# PowerSchematic.net
KiCad netlist of a schematic drawn in Altium Designer
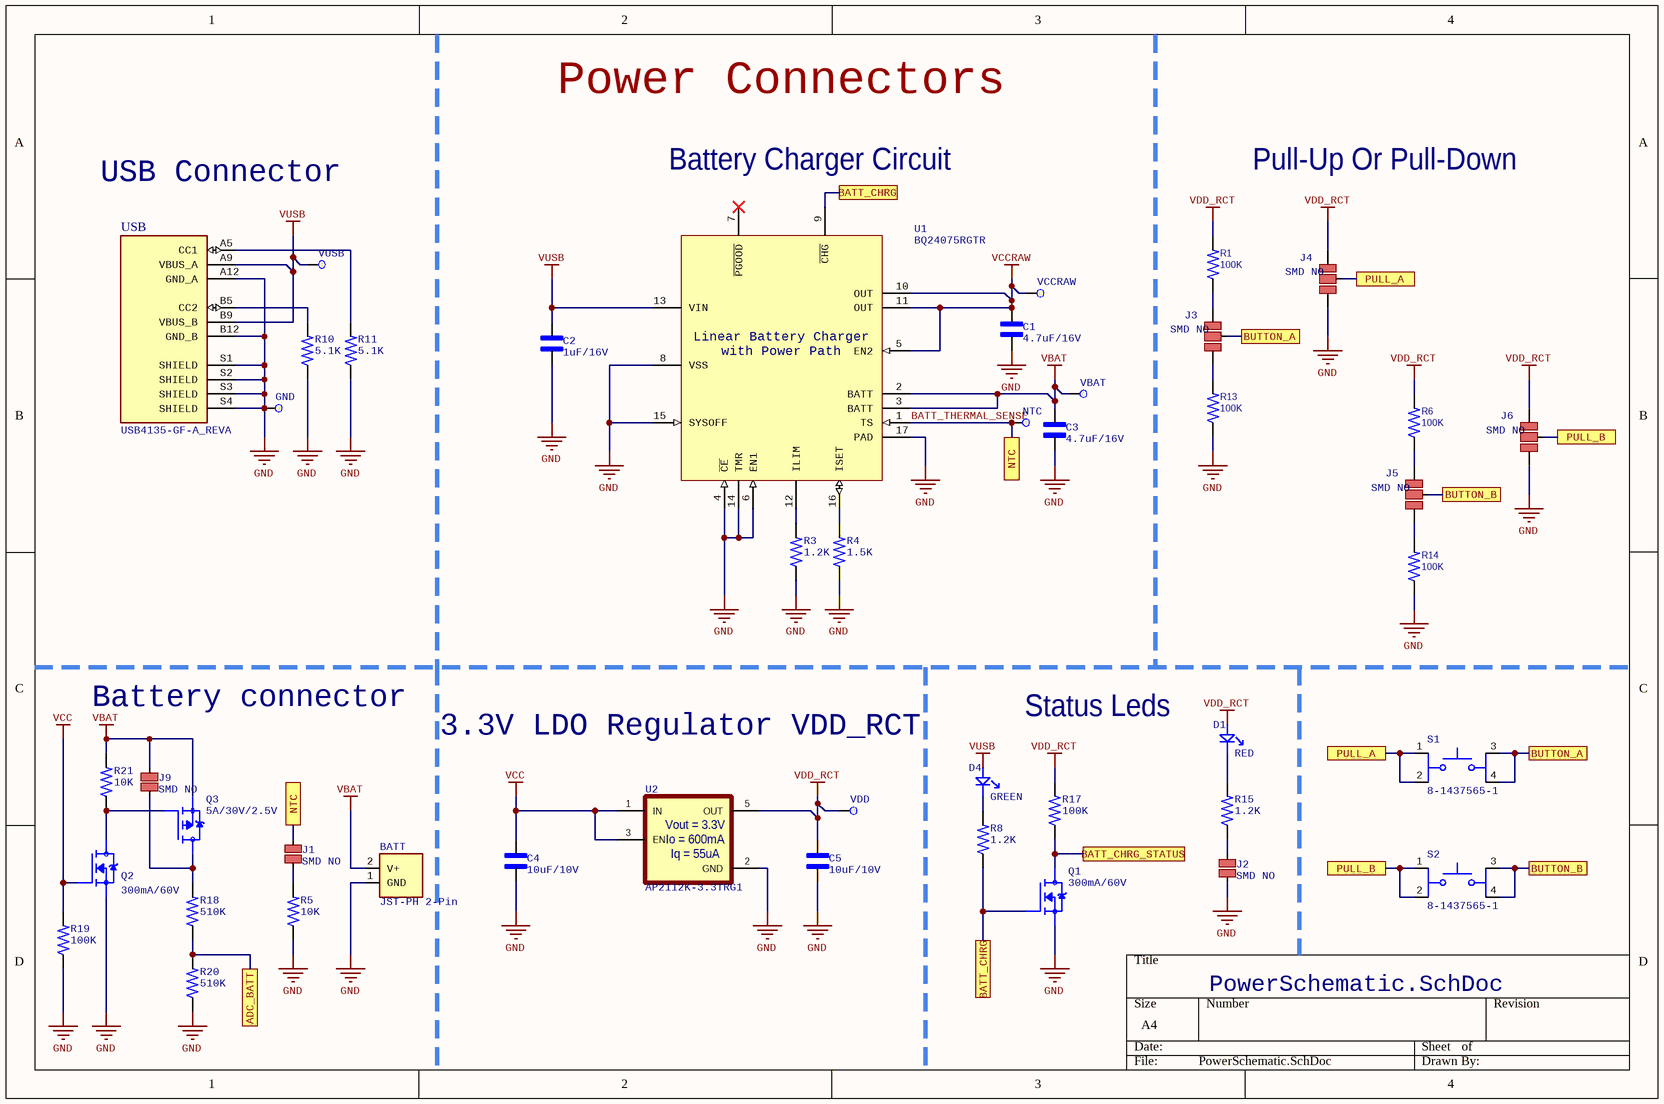
[diagram p0: PowerSchematic.SchDoc]

(export (version "E")
  (design (tool "Eeschema 10.0.6"))
  (components
    (comp (ref "BATT")
      (value "JST-PH 2-Pin")
      (footprint "JST_B2B-PH-K-S(LF)(SN)")
      (fields
        (field (name "MANUFACTURER") "JST")
        (field (name "MANUFACTURER PART NUMBER") "B2B-PH-K-S(LF)(SN)")
      )
      (libsource (lib "Connectors") (part "JST-PH 2-Pin"))
    )
    (comp (ref "C1")
      (value "4.7uF/16V")
      (footprint "C0603")
      (description "0603 4.7 uF 16 V ±10% Tolerance X5R Multilayer Ceramic Capacitor")
      (fields
        (field (name "MANUFACTURER") "Murata")
        (field (name "MANUFACTURER PART NUMBER") "GRT188R61C475KE13D")
      )
      (libsource (lib "Capacitors") (part "C0603 4.7uF/16V"))
    )
    (comp (ref "C2")
      (value "1uF/16V")
      (footprint "C0603")
      (description "MLCC 1uF 16V X5R 10% SMD 0603 85C Paper T/R")
      (fields
        (field (name "MANUFACTURER") "Yageo")
        (field (name "MANUFACTURER PART NUMBER") "CC0603KRX5R7BB105")
      )
      (libsource (lib "Capacitors") (part "C0603 1uF/16V X5R"))
    )
    (comp (ref "C3")
      (value "4.7uF/16V")
      (footprint "C0603")
      (description "0603 4.7 uF 16 V ±10% Tolerance X5R Multilayer Ceramic Capacitor")
      (fields
        (field (name "MANUFACTURER") "Murata")
        (field (name "MANUFACTURER PART NUMBER") "GRT188R61C475KE13D")
      )
      (libsource (lib "Capacitors") (part "C0603 4.7uF/16V"))
    )
    (comp (ref "C4")
      (value "10uF/10V")
      (footprint "C0603")
      (description "MLCC 10uF 10V X5R 20% 0603")
      (fields
        (field (name "MANUFACTURER") "Samsung")
        (field (name "MANUFACTURER PART NUMBER") "CL10A106MP8NNND")
      )
      (libsource (lib "Capacitors") (part "C0603 10uF/10V"))
    )
    (comp (ref "C5")
      (value "10uF/10V")
      (footprint "C0603")
      (description "MLCC 10uF 10V X5R 20% 0603")
      (fields
        (field (name "MANUFACTURER") "Samsung")
        (field (name "MANUFACTURER PART NUMBER") "CL10A106MP8NNND")
      )
      (libsource (lib "Capacitors") (part "C0603 10uF/10V"))
    )
    (comp (ref "D1")
      (value "RED")
      (footprint "LED 0603")
      (description "Red 625nm LED Indication - Discrete 2V 0603")
      (fields
        (field (name "MANUFACTURER") "Wurth Electronics")
        (field (name "MANUFACTURER PART NUMBER") "150060RS55040")
      )
      (libsource (lib "LED") (part "LED 0603 RED"))
    )
    (comp (ref "D4")
      (value "GREEN")
      (footprint "LED 0603")
      (description "Green 575nm LED Indication - Discrete 2V 0603")
      (fields
        (field (name "MANUFACTURER") "Wurth Electronics")
        (field (name "MANUFACTURER PART NUMBER") "150060VS55040")
      )
      (libsource (lib "LED") (part "LED 0603 GREEN"))
    )
    (comp (ref "GND")
      (value "Test point 1.2mm")
      (footprint "TEST_POINT_1.2MM")
      (description "SMD test point")
      (libsource (lib "Connectors") (part "Test point"))
    )
    (comp (ref "J1")
      (value "SMD NO")
      (footprint "JUMPER_SMD_NO")
      (libsource (lib "Jumpers") (part "JUMPER_SMD_NO"))
    )
    (comp (ref "J2")
      (value "SMD NO")
      (footprint "JUMPER_SMD_NO")
      (libsource (lib "Jumpers") (part "JUMPER_SMD_NO"))
    )
    (comp (ref "J3")
      (value "SMD NO")
      (footprint "JUMPER_SMD_NO_2WAY")
      (libsource (lib "Jumpers") (part "JUMPER_SMD_NO_2WAY"))
    )
    (comp (ref "J4")
      (value "SMD NO")
      (footprint "JUMPER_SMD_NO_2WAY")
      (libsource (lib "Jumpers") (part "JUMPER_SMD_NO_2WAY"))
    )
    (comp (ref "J5")
      (value "SMD NO")
      (footprint "JUMPER_SMD_NO_2WAY")
      (libsource (lib "Jumpers") (part "JUMPER_SMD_NO_2WAY"))
    )
    (comp (ref "J6")
      (value "SMD NO")
      (footprint "JUMPER_SMD_NO_2WAY")
      (libsource (lib "Jumpers") (part "JUMPER_SMD_NO_2WAY"))
    )
    (comp (ref "J9")
      (value "SMD NO")
      (footprint "JUMPER_SMD_NO")
      (libsource (lib "Jumpers") (part "JUMPER_SMD_NO"))
    )
    (comp (ref "NTC")
      (value "Test point 1.2mm")
      (footprint "TEST_POINT_1.2MM")
      (description "SMD test point")
      (libsource (lib "Connectors") (part "Test point"))
    )
    (comp (ref "Q1")
      (value "300mA/60V")
      (footprint "SOT-23-3")
      (description "Trans MOSFET N-CH 60V 0.3A 3-Pin TO-236AB T/R")
      (fields (field (name "MANUFACTURER") "Nexperia") (field (name "MANUFACTURER PART NUMBER") "2N7002,215"))
      (libsource (lib "DiscreteSemi") (part "MOSFET N-CH 2N7002,215"))
    )
    (comp (ref "Q2")
      (value "300mA/60V")
      (footprint "SOT-23-3")
      (description "Trans MOSFET N-CH 60V 0.3A 3-Pin TO-236AB T/R")
      (fields (field (name "MANUFACTURER") "Nexperia") (field (name "MANUFACTURER PART NUMBER") "2N7002,215"))
      (libsource (lib "DiscreteSemi") (part "MOSFET N-CH 2N7002,215"))
    )
    (comp (ref "Q3")
      (value "5A/30V/2.5V")
      (footprint "SOT-23-3")
      (description "P-Channel 30 V 42 mOhm 22 nC Surface Mount Power Mosfet - SOT-23-3")
      (fields
        (field (name "MANUFACTURER") "Vishay Semiconductors")
        (field (name "MANUFACTURER PART NUMBER") "Si2347DS-T1-GE3")
      )
      (libsource (lib "DiscreteSemi") (part "MOSFET P-CH 30V/5A SI2347DS-T1-GE3"))
    )
    (comp (ref "R1")
      (value "100K")
      (footprint "R0603")
      (description "RES 0603 100K OHM 1% 1/10W")
      (fields
        (field (name "MANUFACTURER") "Yageo")
        (field (name "MANUFACTURER PART NUMBER") "RC0603FR-07100KL")
      )
      (libsource (lib "Resistors") (part "R0603 100K"))
    )
    (comp (ref "R3")
      (value "1.2K")
      (footprint "R0603")
      (description "RES 0603 1.2K OHM 1% 1/10W")
      (fields
        (field (name "MANUFACTURER") "Yageo")
        (field (name "MANUFACTURER PART NUMBER") "RC0603FR-071K2L")
      )
      (libsource (lib "Resistors") (part "R0603 1.2K"))
    )
    (comp (ref "R4")
      (value "1.5K")
      (footprint "R0603")
      (description "RES 0603 1.5K OHM 0.5% 1/10W")
      (fields
        (field (name "MANUFACTURER") "Yageo")
        (field (name "MANUFACTURER PART NUMBER") "RC0603FR-071K5L")
      )
      (libsource (lib "Resistors") (part "R0603 1.5K"))
    )
    (comp (ref "R5")
      (value "10K")
      (footprint "R0603")
      (description "SMD Chip Resistor, 10 kOhm, ± 1%, 100 mW, 0603 [1608 Metric], Thick Film, Anti-Sulfur")
      (fields
        (field (name "MANUFACTURER") "Yageo")
        (field (name "MANUFACTURER PART NUMBER") "AF0603FR-0710KL")
      )
      (libsource (lib "Resistors") (part "R0603 10K"))
    )
    (comp (ref "R6")
      (value "100K")
      (footprint "R0603")
      (description "RES 0603 100K OHM 1% 1/10W")
      (fields
        (field (name "MANUFACTURER") "Yageo")
        (field (name "MANUFACTURER PART NUMBER") "RC0603FR-07100KL")
      )
      (libsource (lib "Resistors") (part "R0603 100K"))
    )
    (comp (ref "R8")
      (value "1.2K")
      (footprint "R0603")
      (description "RES 0603 1.2K OHM 1% 1/10W")
      (fields
        (field (name "MANUFACTURER") "Yageo")
        (field (name "MANUFACTURER PART NUMBER") "RC0603FR-071K2L")
      )
      (libsource (lib "Resistors") (part "R0603 1.2K"))
    )
    (comp (ref "R10")
      (value "5.1K")
      (footprint "R0603")
      (description "RES 0603 5.1K OHM 1% 1/10W")
      (fields
        (field (name "MANUFACTURER") "Yageo")
        (field (name "MANUFACTURER PART NUMBER") "RC0603FR-075K1L")
      )
      (libsource (lib "Resistors") (part "R0603 5.1K"))
    )
    (comp (ref "R11")
      (value "5.1K")
      (footprint "R0603")
      (description "RES 0603 5.1K OHM 1% 1/10W")
      (fields
        (field (name "MANUFACTURER") "Yageo")
        (field (name "MANUFACTURER PART NUMBER") "RC0603FR-075K1L")
      )
      (libsource (lib "Resistors") (part "R0603 5.1K"))
    )
    (comp (ref "R13")
      (value "100K")
      (footprint "R0603")
      (description "RES 0603 100K OHM 1% 1/10W")
      (fields
        (field (name "MANUFACTURER") "Yageo")
        (field (name "MANUFACTURER PART NUMBER") "RC0603FR-07100KL")
      )
      (libsource (lib "Resistors") (part "R0603 100K"))
    )
    (comp (ref "R14")
      (value "100K")
      (footprint "R0603")
      (description "RES 0603 100K OHM 1% 1/10W")
      (fields
        (field (name "MANUFACTURER") "Yageo")
        (field (name "MANUFACTURER PART NUMBER") "RC0603FR-07100KL")
      )
      (libsource (lib "Resistors") (part "R0603 100K"))
    )
    (comp (ref "R15")
      (value "1.2K")
      (footprint "R0603")
      (description "RES 0603 1.2K OHM 1% 1/10W")
      (fields
        (field (name "MANUFACTURER") "Yageo")
        (field (name "MANUFACTURER PART NUMBER") "RC0603FR-071K2L")
      )
      (libsource (lib "Resistors") (part "R0603 1.2K"))
    )
    (comp (ref "R17")
      (value "100K")
      (footprint "R0603")
      (description "RES 0603 100K OHM 1% 1/10W")
      (fields
        (field (name "MANUFACTURER") "Yageo")
        (field (name "MANUFACTURER PART NUMBER") "RC0603FR-07100KL")
      )
      (libsource (lib "Resistors") (part "R0603 100K"))
    )
    (comp (ref "R18")
      (value "510K")
      (footprint "R0603")
      (description "RES 0603 510K OHM 1% 1/10W")
      (fields
        (field (name "MANUFACTURER") "TE Connectivity")
        (field (name "MANUFACTURER PART NUMBER") "CPF0603B510KE")
      )
      (libsource (lib "Resistors") (part "R0603 510K"))
    )
    (comp (ref "R19")
      (value "100K")
      (footprint "R0603")
      (description "RES 0603 100K OHM 1% 1/10W")
      (fields
        (field (name "MANUFACTURER") "Yageo")
        (field (name "MANUFACTURER PART NUMBER") "RC0603FR-07100KL")
      )
      (libsource (lib "Resistors") (part "R0603 100K"))
    )
    (comp (ref "R20")
      (value "510K")
      (footprint "R0603")
      (description "RES 0603 510K OHM 1% 1/10W")
      (fields
        (field (name "MANUFACTURER") "TE Connectivity")
        (field (name "MANUFACTURER PART NUMBER") "CPF0603B510KE")
      )
      (libsource (lib "Resistors") (part "R0603 510K"))
    )
    (comp (ref "R21")
      (value "10K")
      (footprint "R0603")
      (description "SMD Chip Resistor, 10 kOhm, ± 1%, 100 mW, 0603 [1608 Metric], Thick Film, Anti-Sulfur")
      (fields
        (field (name "MANUFACTURER") "Yageo")
        (field (name "MANUFACTURER PART NUMBER") "AF0603FR-0710KL")
      )
      (libsource (lib "Resistors") (part "R0603 10K"))
    )
    (comp (ref "S1")
      (value "8-1437565-1")
      (footprint "SW_8-1437565-1")
      (description "Switch Tactile OFF (ON) SPST Round Button Gull Wing 0.05A 24VDC 1.57N SMD T/R")
      (fields (field (name "MANUFACTURER") "TE Connectivity Alcoswitch"))
      (libsource (lib "Switches") (part "8-1437565-1"))
    )
    (comp (ref "S2")
      (value "8-1437565-1")
      (footprint "SW_8-1437565-1")
      (description "Switch Tactile OFF (ON) SPST Round Button Gull Wing 0.05A 24VDC 1.57N SMD T/R")
      (fields (field (name "MANUFACTURER") "TE Connectivity Alcoswitch"))
      (libsource (lib "Switches") (part "8-1437565-1"))
    )
    (comp (ref "U1")
      (value "BQ24075RGTR")
      (footprint "VQFN16")
      (description "IC LI-ION CHARGE MGMT 16-QFN")
      (fields (field (name "MANUFACTURER") "Texas Instruments"))
      (libsource (lib "IC Power") (part "BQ24075RGTR"))
    )
    (comp (ref "U2")
      (value "AP2112K-3.3TRG1")
      (footprint "SOT-25-5")
      (description "IC REG LINEAR 3.3V 600MA SOT25")
      (fields (field (name "MANUFACTURER") "Diodes"))
      (libsource (lib "IC Power") (part "AP2112K-3.3TRG1"))
    )
    (comp (ref "USB")
      (value "USB4135-GF-A_REVA")
      (footprint "GCT_USB4135 16-pin")
      (description "Usb C Rec Gf Ra 6P SMT & SMT She")
      (libsource (lib "Connectors") (part "USB4135-GF-A_REVA"))
    )
    (comp (ref "VBAT")
      (value "Test point 1.2mm")
      (footprint "TEST_POINT_1.2MM")
      (description "SMD test point")
      (libsource (lib "Connectors") (part "Test point"))
    )
    (comp (ref "VCCRAW")
      (value "Test point 1.2mm")
      (footprint "TEST_POINT_1.2MM")
      (description "SMD test point")
      (libsource (lib "Connectors") (part "Test point"))
    )
    (comp (ref "VDD")
      (value "Test point 1.2mm")
      (footprint "TEST_POINT_1.2MM")
      (description "SMD test point")
      (libsource (lib "Connectors") (part "Test point"))
    )
    (comp (ref "VUSB")
      (value "Test point 1.2mm")
      (footprint "TEST_POINT_1.2MM")
      (description "SMD test point")
      (libsource (lib "Connectors") (part "Test point"))
    )
  )
  (nets
    (net (code "1") (name "/ADC_BATT") (class "Default")
      (node (ref "R18") (pin "1") (pinfunction "1_1") (pintype "passive"))
      (node (ref "R20") (pin "2") (pinfunction "2_2") (pintype "passive"))
    )
    (net (code "2") (name "/BATT_CHRG") (class "Default")
      (node (ref "Q1") (pin "1") (pinfunction "G_1") (pintype "passive"))
      (node (ref "R8") (pin "1") (pinfunction "1_1") (pintype "passive"))
      (node (ref "U1") (pin "9") (pinfunction "CHG_9") (pintype "open_collector"))
    )
    (net (code "3") (name "/BATT_CHRG_STATUS") (class "Default")
      (node (ref "Q1") (pin "3") (pinfunction "D_3") (pintype "passive"))
      (node (ref "R17") (pin "1") (pinfunction "1_1") (pintype "passive"))
    )
    (net (code "4") (name "/BATT_THERMAL_SENSE") (class "Default")
      (node (ref "J1") (pin "1") (pinfunction "1_1") (pintype "passive"))
      (node (ref "NTC") (pin "1") (pinfunction "1_1") (pintype "passive"))
      (node (ref "U1") (pin "1") (pinfunction "TS_1") (pintype "input"))
    )
    (net (code "5") (name "/BUTTON_A") (class "Default")
      (node (ref "J3") (pin "2") (pinfunction "2_2") (pintype "passive"))
      (node (ref "S1") (pin "3") (pinfunction "3_3") (pintype "passive"))
      (node (ref "S1") (pin "4") (pinfunction "4_4") (pintype "passive"))
    )
    (net (code "6") (name "/BUTTON_B") (class "Default")
      (node (ref "J5") (pin "2") (pinfunction "2_2") (pintype "passive"))
      (node (ref "S2") (pin "3") (pinfunction "3_3") (pintype "passive"))
      (node (ref "S2") (pin "4") (pinfunction "4_4") (pintype "passive"))
    )
    (net (code "7") (name "/PULL_A") (class "Default")
      (node (ref "J4") (pin "2") (pinfunction "2_2") (pintype "passive"))
      (node (ref "S1") (pin "1") (pinfunction "1_1") (pintype "passive"))
      (node (ref "S1") (pin "2") (pinfunction "2_2") (pintype "passive"))
    )
    (net (code "8") (name "/PULL_B") (class "Default")
      (node (ref "J6") (pin "2") (pinfunction "2_2") (pintype "passive"))
      (node (ref "S2") (pin "1") (pinfunction "1_1") (pintype "passive"))
      (node (ref "S2") (pin "2") (pinfunction "2_2") (pintype "passive"))
    )
    (net (code "9") (name "GND") (class "Default")
      (node (ref "BATT") (pin "1") (pinfunction "GND_1") (pintype "passive"))
      (node (ref "C1") (pin "2") (pinfunction "2_2") (pintype "passive"))
      (node (ref "C2") (pin "2") (pinfunction "2_2") (pintype "passive"))
      (node (ref "C3") (pin "2") (pinfunction "2_2") (pintype "passive"))
      (node (ref "C4") (pin "2") (pinfunction "2_2") (pintype "passive"))
      (node (ref "C5") (pin "2") (pinfunction "2_2") (pintype "passive"))
      (node (ref "GND") (pin "1") (pinfunction "1_1") (pintype "passive"))
      (node (ref "J2") (pin "2") (pinfunction "2_2") (pintype "passive"))
      (node (ref "J4") (pin "1") (pinfunction "1_1") (pintype "passive"))
      (node (ref "J6") (pin "1") (pinfunction "1_1") (pintype "passive"))
      (node (ref "Q1") (pin "2") (pinfunction "S_2") (pintype "passive"))
      (node (ref "Q2") (pin "2") (pinfunction "S_2") (pintype "passive"))
      (node (ref "R10") (pin "1") (pinfunction "1_1") (pintype "passive"))
      (node (ref "R11") (pin "1") (pinfunction "1_1") (pintype "passive"))
      (node (ref "R13") (pin "1") (pinfunction "1_1") (pintype "passive"))
      (node (ref "R14") (pin "1") (pinfunction "1_1") (pintype "passive"))
      (node (ref "R19") (pin "1") (pinfunction "1_1") (pintype "passive"))
      (node (ref "R20") (pin "1") (pinfunction "1_1") (pintype "passive"))
      (node (ref "R3") (pin "1") (pinfunction "1_1") (pintype "passive"))
      (node (ref "R4") (pin "1") (pinfunction "1_1") (pintype "passive"))
      (node (ref "R5") (pin "1") (pinfunction "1_1") (pintype "passive"))
      (node (ref "U1") (pin "14") (pinfunction "TMR_14") (pintype "passive"))
      (node (ref "U1") (pin "15") (pinfunction "SYSOFF_15") (pintype "input"))
      (node (ref "U1") (pin "17") (pinfunction "PAD_17") (pintype "passive"))
      (node (ref "U1") (pin "4") (pinfunction "CE_4") (pintype "input"))
      (node (ref "U1") (pin "6") (pinfunction "EN1_6") (pintype "input"))
      (node (ref "U1") (pin "8") (pinfunction "VSS_8") (pintype "power_in"))
      (node (ref "U2") (pin "2") (pinfunction "GND_2") (pintype "power_in"))
      (node (ref "USB") (pin "A12") (pinfunction "GND_A_A12") (pintype "power_in"))
      (node (ref "USB") (pin "B12") (pinfunction "GND_B_B12") (pintype "power_in"))
      (node (ref "USB") (pin "S1") (pinfunction "SHIELD_S1") (pintype "passive"))
      (node (ref "USB") (pin "S2") (pinfunction "SHIELD_S2") (pintype "passive"))
      (node (ref "USB") (pin "S3") (pinfunction "SHIELD_S3") (pintype "passive"))
      (node (ref "USB") (pin "S4") (pinfunction "SHIELD_S4") (pintype "passive"))
    )
    (net (code "10") (name "Net-(D1-K)") (class "Default")
      (node (ref "D1") (pin "2") (pinfunction "K_2") (pintype "passive"))
      (node (ref "R15") (pin "2") (pinfunction "2_2") (pintype "passive"))
    )
    (net (code "11") (name "Net-(D4-K)") (class "Default")
      (node (ref "D4") (pin "2") (pinfunction "K_2") (pintype "passive"))
      (node (ref "R8") (pin "2") (pinfunction "2_2") (pintype "passive"))
    )
    (net (code "12") (name "Net-(J1-Pad2)") (class "Default")
      (node (ref "J1") (pin "2") (pinfunction "2_2") (pintype "passive"))
      (node (ref "R5") (pin "2") (pinfunction "2_2") (pintype "passive"))
    )
    (net (code "13") (name "Net-(J2-Pad1)") (class "Default")
      (node (ref "J2") (pin "1") (pinfunction "1_1") (pintype "passive"))
      (node (ref "R15") (pin "1") (pinfunction "1_1") (pintype "passive"))
    )
    (net (code "14") (name "Net-(J3-Pad1)") (class "Default")
      (node (ref "J3") (pin "1") (pinfunction "1_1") (pintype "passive"))
      (node (ref "R13") (pin "2") (pinfunction "2_2") (pintype "passive"))
    )
    (net (code "15") (name "Net-(J3-Pad3)") (class "Default")
      (node (ref "J3") (pin "3") (pinfunction "3_3") (pintype "passive"))
      (node (ref "R1") (pin "1") (pinfunction "1_1") (pintype "passive"))
    )
    (net (code "16") (name "Net-(J5-Pad1)") (class "Default")
      (node (ref "J5") (pin "1") (pinfunction "1_1") (pintype "passive"))
      (node (ref "R14") (pin "2") (pinfunction "2_2") (pintype "passive"))
    )
    (net (code "17") (name "Net-(J5-Pad3)") (class "Default")
      (node (ref "J5") (pin "3") (pinfunction "3_3") (pintype "passive"))
      (node (ref "R6") (pin "1") (pinfunction "1_1") (pintype "passive"))
    )
    (net (code "18") (name "Net-(Q2-D)") (class "Default")
      (node (ref "Q2") (pin "3") (pinfunction "D_3") (pintype "passive"))
      (node (ref "Q3") (pin "1") (pinfunction "G_1") (pintype "passive"))
      (node (ref "R21") (pin "1") (pinfunction "1_1") (pintype "passive"))
    )
    (net (code "19") (name "Net-(Q3-D)") (class "Default")
      (node (ref "J9") (pin "2") (pinfunction "2_2") (pintype "passive"))
      (node (ref "Q3") (pin "3") (pinfunction "D_3") (pintype "passive"))
      (node (ref "R18") (pin "2") (pinfunction "2_2") (pintype "passive"))
    )
    (net (code "20") (name "Net-(U1-ILIM)") (class "Default")
      (node (ref "R3") (pin "2") (pinfunction "2_2") (pintype "passive"))
      (node (ref "U1") (pin "12") (pinfunction "ILIM_12") (pintype "passive"))
    )
    (net (code "21") (name "Net-(U1-ISET)") (class "Default")
      (node (ref "R4") (pin "2") (pinfunction "2_2") (pintype "passive"))
      (node (ref "U1") (pin "16") (pinfunction "ISET_16") (pintype "bidirectional"))
    )
    (net (code "22") (name "Net-(USB-CC1)") (class "Default")
      (node (ref "R11") (pin "2") (pinfunction "2_2") (pintype "passive"))
      (node (ref "USB") (pin "A5") (pinfunction "CC1_A5") (pintype "bidirectional"))
    )
    (net (code "23") (name "Net-(USB-CC2)") (class "Default")
      (node (ref "R10") (pin "2") (pinfunction "2_2") (pintype "passive"))
      (node (ref "USB") (pin "B5") (pinfunction "CC2_B5") (pintype "bidirectional"))
    )
    (net (code "24") (name "VBAT") (class "Default")
      (node (ref "BATT") (pin "2") (pinfunction "V+_2") (pintype "passive"))
      (node (ref "C3") (pin "1") (pinfunction "1_1") (pintype "passive"))
      (node (ref "J9") (pin "1") (pinfunction "1_1") (pintype "passive"))
      (node (ref "Q3") (pin "2") (pinfunction "S_2") (pintype "passive"))
      (node (ref "R21") (pin "2") (pinfunction "2_2") (pintype "passive"))
      (node (ref "U1") (pin "2") (pinfunction "BATT_2") (pintype "power_in"))
      (node (ref "U1") (pin "3") (pinfunction "BATT_3") (pintype "power_in"))
      (node (ref "VBAT") (pin "1") (pinfunction "1_1") (pintype "passive"))
    )
    (net (code "25") (name "VCC") (class "Default")
      (node (ref "C4") (pin "1") (pinfunction "1_1") (pintype "passive"))
      (node (ref "Q2") (pin "1") (pinfunction "G_1") (pintype "passive"))
      (node (ref "R19") (pin "2") (pinfunction "2_2") (pintype "passive"))
      (node (ref "U2") (pin "1") (pinfunction "IN_1") (pintype "power_in"))
      (node (ref "U2") (pin "3") (pinfunction "EN_3") (pintype "passive"))
    )
    (net (code "26") (name "VCCRAW") (class "Default")
      (node (ref "C1") (pin "1") (pinfunction "1_1") (pintype "passive"))
      (node (ref "U1") (pin "10") (pinfunction "OUT_10") (pintype "power_in"))
      (node (ref "U1") (pin "11") (pinfunction "OUT_11") (pintype "power_in"))
      (node (ref "U1") (pin "5") (pinfunction "EN2_5") (pintype "input"))
      (node (ref "VCCRAW") (pin "1") (pinfunction "1_1") (pintype "passive"))
    )
    (net (code "27") (name "VDD_RCT") (class "Default")
      (node (ref "C5") (pin "1") (pinfunction "1_1") (pintype "passive"))
      (node (ref "D1") (pin "1") (pinfunction "A_1") (pintype "passive"))
      (node (ref "J4") (pin "3") (pinfunction "3_3") (pintype "passive"))
      (node (ref "J6") (pin "3") (pinfunction "3_3") (pintype "passive"))
      (node (ref "R1") (pin "2") (pinfunction "2_2") (pintype "passive"))
      (node (ref "R17") (pin "2") (pinfunction "2_2") (pintype "passive"))
      (node (ref "R6") (pin "2") (pinfunction "2_2") (pintype "passive"))
      (node (ref "U2") (pin "5") (pinfunction "OUT_5") (pintype "power_in"))
      (node (ref "VDD") (pin "1") (pinfunction "1_1") (pintype "passive"))
    )
    (net (code "28") (name "VUSB") (class "Default")
      (node (ref "C2") (pin "1") (pinfunction "1_1") (pintype "passive"))
      (node (ref "D4") (pin "1") (pinfunction "A_1") (pintype "passive"))
      (node (ref "U1") (pin "13") (pinfunction "VIN_13") (pintype "power_in"))
      (node (ref "USB") (pin "A9") (pinfunction "VBUS_A_A9") (pintype "power_in"))
      (node (ref "USB") (pin "B9") (pinfunction "VBUS_B_B9") (pintype "power_in"))
      (node (ref "VUSB") (pin "1") (pinfunction "1_1") (pintype "passive"))
    )
    (net (code "29") (name "unconnected-(U1-PGOOD-Pad7)") (class "Default")
      (node (ref "U1") (pin "7") (pinfunction "PGOOD_7") (pintype "open_collector+no_connect"))
    )
  )
)
